# rapidshark-flywheel-controller-mk-1_4.net
KiCad netlist of a schematic drawn in EAGLE
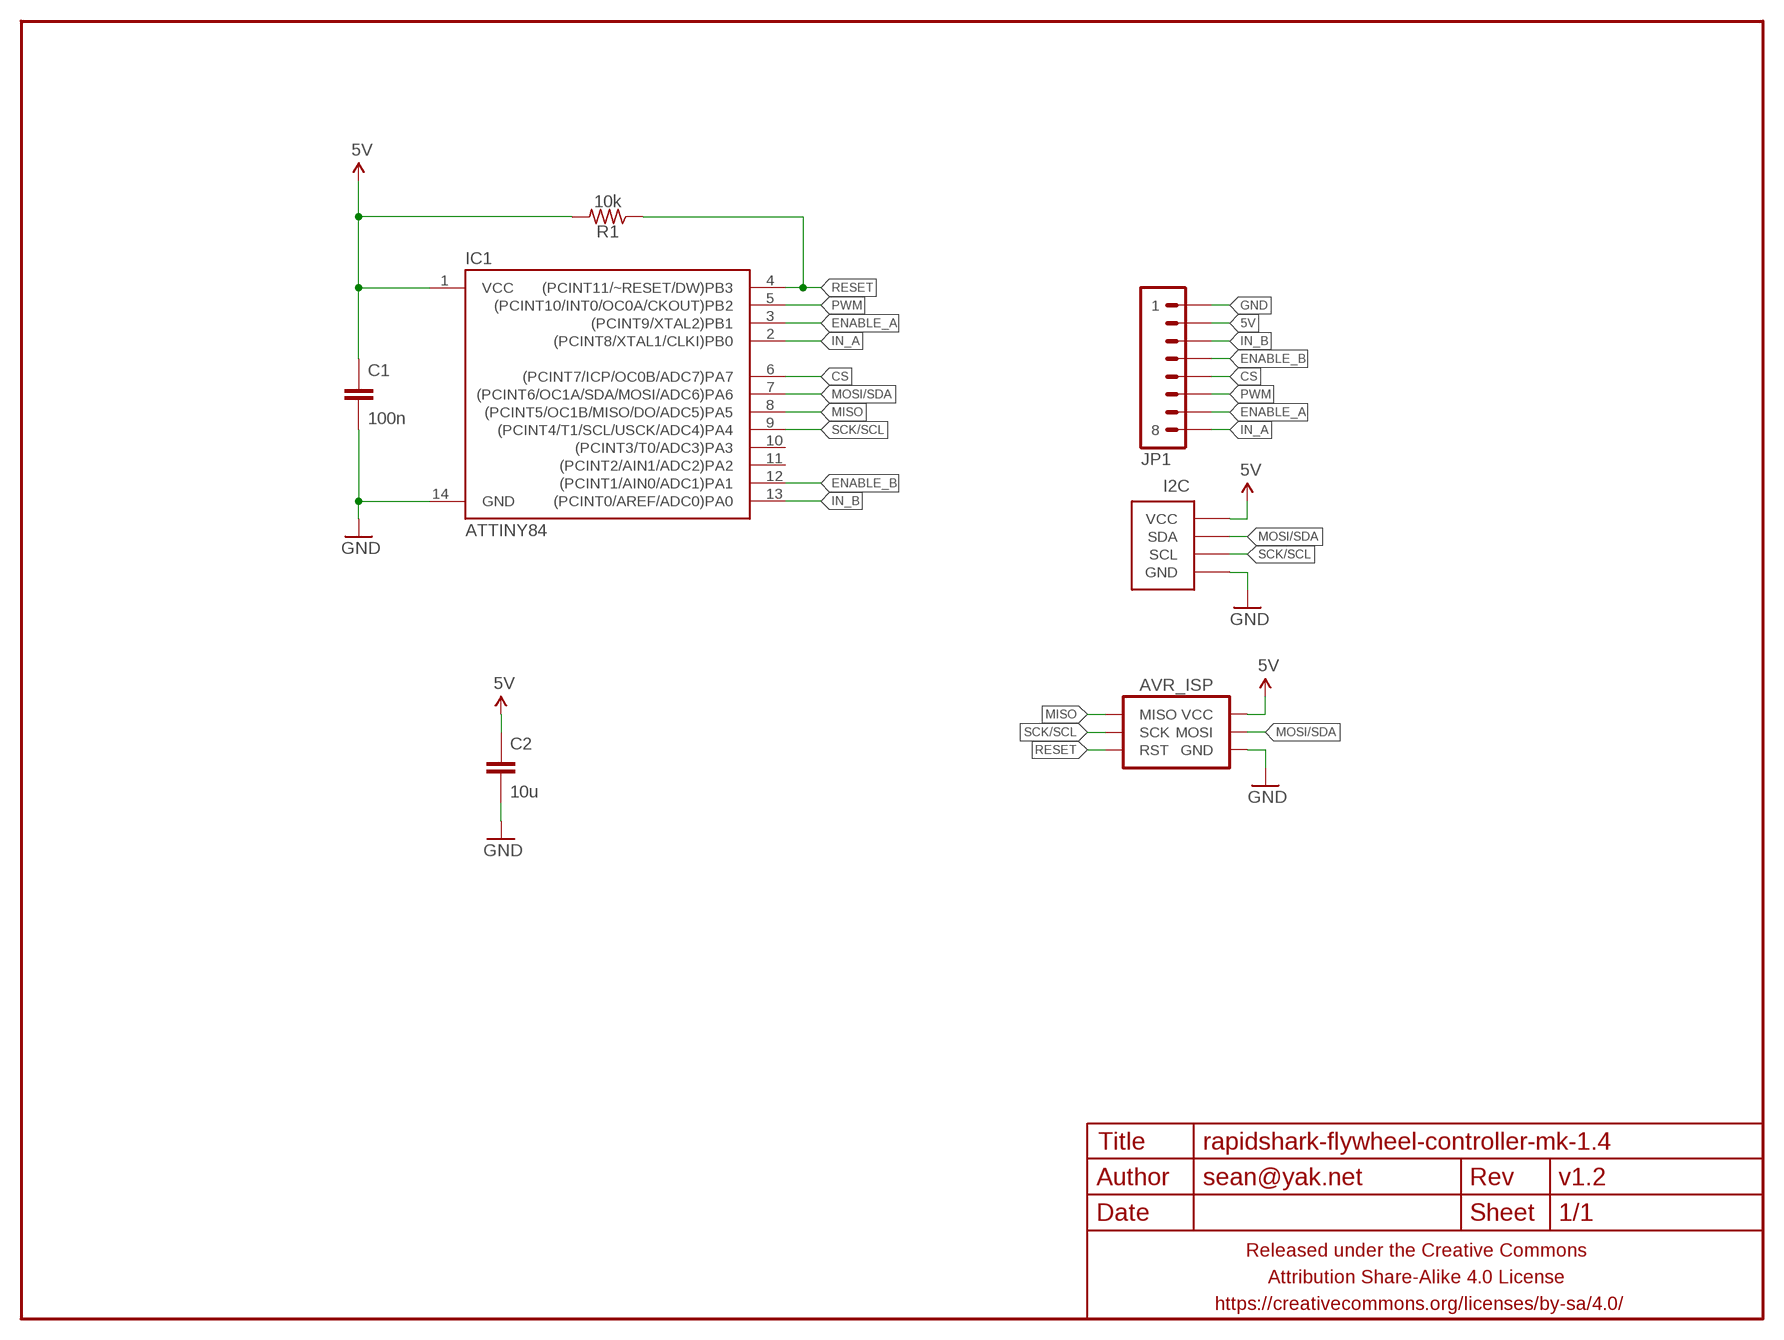
[diagram p0: schematic, sheet 1]

(export (version "E")
  (design (tool "Eeschema 10.0.6"))
  (components
    (comp (ref "AVR_ISP")
      (value "AVR_SPI_PRG_6PTH")
      (footprint "eagle-import:2X3")
      (libsource (lib "eagle-import") (part "AVR_SPI_PRG_6PTH"))
    )
    (comp (ref "C1")
      (value "100n")
      (footprint "eagle-import:CAPCER-RAD-PTH-2.54MM")
      (libsource (lib "eagle-import") (part "CAPACITOR-CERAMICPTH-RAD-2.54MM"))
    )
    (comp (ref "C2")
      (value "10u")
      (footprint "eagle-import:CAPCER-RAD-PTH-5.08MM")
      (libsource (lib "eagle-import") (part "CAPACITOR-CERAMICPTH-RAD-5.08MM"))
    )
    (comp (ref "FRAME1")
      (value "FRAME-LETTERNO_PACKAGE")
      (footprint "eagle-import:DUMMY")
      (fields (field (name "DESIGNER") "sean@yak.net") (field (name "VERSION") "v1.2"))
      (libsource (lib "eagle-import") (part "FRAME-LETTERNO_PACKAGE"))
    )
    (comp (ref "I2C")
      (value "M04-I2CJST-4-PH-RA-CENTERED")
      (footprint "eagle-import:1X04-JST-PH-RA-PTH-I2C-CENTERED")
      (libsource (lib "eagle-import") (part "M04-I2CJST-4-PH-RA-CENTERED"))
    )
    (comp (ref "IC1")
      (value "ATTINY84")
      (footprint "eagle-import:SO14")
      (libsource (lib "eagle-import") (part "ATTINY84"))
    )
    (comp (ref "JP1")
      (value "M081X08")
      (footprint "eagle-import:1X08")
      (libsource (lib "eagle-import") (part "M081X08"))
    )
    (comp (ref "R1")
      (value "10k")
      (footprint "eagle-import:RESISTOR-AXIAL-PTH-5.08MM")
      (libsource (lib "eagle-import") (part "RESISTORPTH-AXIAL-5.08MM"))
    )
  )
  (nets
    (net (code "1") (name "5V") (class "Default")
      (node (ref "AVR_ISP") (pin "2") (pinfunction "VCC_2") (pintype "passive"))
      (node (ref "C1") (pin "1") (pinfunction "1_1") (pintype "passive"))
      (node (ref "C2") (pin "1") (pinfunction "1_1") (pintype "passive"))
      (node (ref "I2C") (pin "2") (pinfunction "VCC_2") (pintype "bidirectional"))
      (node (ref "IC1") (pin "1") (pinfunction "VCC_1") (pintype "bidirectional"))
      (node (ref "JP1") (pin "2") (pinfunction "2_2") (pintype "passive"))
      (node (ref "R1") (pin "P$2") (pinfunction "2_P$2") (pintype "passive"))
    )
    (net (code "2") (name "CS") (class "Default")
      (node (ref "IC1") (pin "6") (pinfunction "(PCINT7/ICP/OC0B/ADC7)PA7_6") (pintype "bidirectional"))
      (node (ref "JP1") (pin "5") (pinfunction "5_5") (pintype "passive"))
    )
    (net (code "3") (name "ENABLE_A") (class "Default")
      (node (ref "IC1") (pin "3") (pinfunction "(PCINT9/XTAL2)PB1_3") (pintype "bidirectional"))
      (node (ref "JP1") (pin "7") (pinfunction "7_7") (pintype "passive"))
    )
    (net (code "4") (name "ENABLE_B") (class "Default")
      (node (ref "IC1") (pin "12") (pinfunction "(PCINT1/AIN0/ADC1)PA1_12") (pintype "bidirectional"))
      (node (ref "JP1") (pin "4") (pinfunction "4_4") (pintype "passive"))
    )
    (net (code "5") (name "GND") (class "Default")
      (node (ref "AVR_ISP") (pin "6") (pinfunction "GND_6") (pintype "passive"))
      (node (ref "C1") (pin "2") (pinfunction "2_2") (pintype "passive"))
      (node (ref "C2") (pin "2") (pinfunction "2_2") (pintype "passive"))
      (node (ref "I2C") (pin "1") (pinfunction "GND_1") (pintype "bidirectional"))
      (node (ref "IC1") (pin "14") (pinfunction "GND_14") (pintype "bidirectional"))
      (node (ref "JP1") (pin "1") (pinfunction "1_1") (pintype "passive"))
    )
    (net (code "6") (name "IN_A") (class "Default")
      (node (ref "IC1") (pin "2") (pinfunction "(PCINT8/XTAL1/CLKI)PB0_2") (pintype "bidirectional"))
      (node (ref "JP1") (pin "8") (pinfunction "8_8") (pintype "passive"))
    )
    (net (code "7") (name "IN_B") (class "Default")
      (node (ref "IC1") (pin "13") (pinfunction "(PCINT0/AREF/ADC0)PA0_13") (pintype "bidirectional"))
      (node (ref "JP1") (pin "3") (pinfunction "3_3") (pintype "passive"))
    )
    (net (code "8") (name "MISO") (class "Default")
      (node (ref "AVR_ISP") (pin "1") (pinfunction "MISO_1") (pintype "passive"))
      (node (ref "IC1") (pin "8") (pinfunction "(PCINT5/OC1B/MISO/DO/ADC5)PA5_8") (pintype "bidirectional"))
    )
    (net (code "9") (name "MOSI{slash}SDA") (class "Default")
      (node (ref "AVR_ISP") (pin "4") (pinfunction "MOSI_4") (pintype "passive"))
      (node (ref "I2C") (pin "3") (pinfunction "SDA_3") (pintype "bidirectional"))
      (node (ref "IC1") (pin "7") (pinfunction "(PCINT6/OC1A/SDA/MOSI/ADC6)PA6_7") (pintype "bidirectional"))
    )
    (net (code "10") (name "PWM") (class "Default")
      (node (ref "IC1") (pin "5") (pinfunction "(PCINT10/INT0/OC0A/CKOUT)PB2_5") (pintype "bidirectional"))
      (node (ref "JP1") (pin "6") (pinfunction "6_6") (pintype "passive"))
    )
    (net (code "11") (name "RESET") (class "Default")
      (node (ref "AVR_ISP") (pin "5") (pinfunction "RST_5") (pintype "passive"))
      (node (ref "IC1") (pin "4") (pinfunction "(PCINT11/~{RESET/DW})PB3_4") (pintype "bidirectional"))
      (node (ref "R1") (pin "P$1") (pinfunction "1_P$1") (pintype "passive"))
    )
    (net (code "12") (name "SCK{slash}SCL") (class "Default")
      (node (ref "AVR_ISP") (pin "3") (pinfunction "SCK_3") (pintype "passive"))
      (node (ref "I2C") (pin "4") (pinfunction "SCL_4") (pintype "bidirectional"))
      (node (ref "IC1") (pin "9") (pinfunction "(PCINT4/T1/SCL/USCK/ADC4)PA4_9") (pintype "bidirectional"))
    )
    (net (code "13") (name "unconnected-(IC1-(PCINT2{slash}AIN1{slash}ADC2)PA2-Pad11)") (class "Default")
      (node (ref "IC1") (pin "11") (pinfunction "(PCINT2/AIN1/ADC2)PA2_11") (pintype "bidirectional"))
    )
    (net (code "14") (name "unconnected-(IC1-(PCINT3{slash}T0{slash}ADC3)PA3-Pad10)") (class "Default")
      (node (ref "IC1") (pin "10") (pinfunction "(PCINT3/T0/ADC3)PA3_10") (pintype "bidirectional"))
    )
  )
)
